# esp32_led.net
KiCad netlist of a schematic drawn in EAGLE
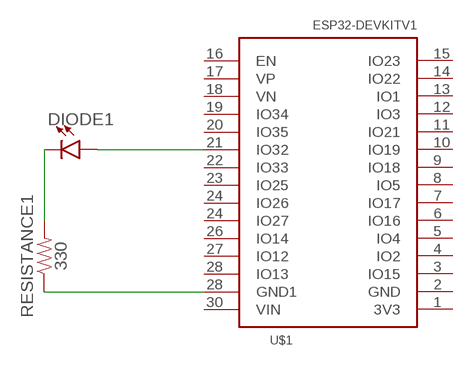
[diagram p0: schematic, sheet 1]

(export (version "E")
  (design (tool "Eeschema 10.0.6"))
  (components
    (comp (ref "DIODE1")
      (value "LED-3MM-NO_SILK")
      (footprint "eagle-import:LED_3MM-NS")
      (libsource (lib "eagle-import") (part "LED-3MM-NO_SILK"))
    )
    (comp (ref "RESISTANCE1")
      (value "330")
      (footprint "eagle-import:AXIAL-0.3")
      (libsource (lib "eagle-import") (part "330OHM-HORIZ-1/10W-5%"))
    )
    (comp (ref "U$1")
      (value "ESP32DEVKITV1")
      (footprint "eagle-import:ESP32-DEVKITV1")
      (libsource (lib "eagle-import") (part "ESP32DEVKITV1"))
    )
  )
  (nets
    (net (code "1") (name "Net-(DIODE1-C)") (class "Default")
      (node (ref "DIODE1") (pin "K") (pinfunction "C_K") (pintype "passive"))
      (node (ref "RESISTANCE1") (pin "P$2") (pinfunction "2_P$2") (pintype "passive"))
    )
    (net (code "2") (name "Net-(RESISTANCE1-1)") (class "Default")
      (node (ref "RESISTANCE1") (pin "P$1") (pinfunction "1_P$1") (pintype "passive"))
      (node (ref "U$1") (pin "28") (pinfunction "GND1_28") (pintype "bidirectional"))
    )
    (net (code "3") (name "Net-(U$1-IO32)") (class "Default")
      (node (ref "DIODE1") (pin "A") (pinfunction "A_A") (pintype "passive"))
      (node (ref "U$1") (pin "21") (pinfunction "IO32_21") (pintype "bidirectional"))
    )
    (net (code "4") (name "unconnected-(U$1-3V3-Pad1)") (class "Default")
      (node (ref "U$1") (pin "1") (pinfunction "3V3_1") (pintype "bidirectional"))
    )
    (net (code "5") (name "unconnected-(U$1-EN-Pad16)") (class "Default")
      (node (ref "U$1") (pin "16") (pinfunction "EN_16") (pintype "bidirectional"))
    )
    (net (code "6") (name "unconnected-(U$1-GND-Pad2)") (class "Default")
      (node (ref "U$1") (pin "2") (pinfunction "GND_2") (pintype "bidirectional"))
    )
    (net (code "7") (name "unconnected-(U$1-IO1-Pad13)") (class "Default")
      (node (ref "U$1") (pin "13") (pinfunction "IO1_13") (pintype "bidirectional"))
    )
    (net (code "8") (name "unconnected-(U$1-IO2-Pad4)") (class "Default")
      (node (ref "U$1") (pin "4") (pinfunction "IO2_4") (pintype "bidirectional"))
    )
    (net (code "9") (name "unconnected-(U$1-IO3-Pad12)") (class "Default")
      (node (ref "U$1") (pin "12") (pinfunction "IO3_12") (pintype "bidirectional"))
    )
    (net (code "10") (name "unconnected-(U$1-IO4-Pad5)") (class "Default")
      (node (ref "U$1") (pin "5") (pinfunction "IO4_5") (pintype "bidirectional"))
    )
    (net (code "11") (name "unconnected-(U$1-IO5-Pad8)") (class "Default")
      (node (ref "U$1") (pin "8") (pinfunction "IO5_8") (pintype "bidirectional"))
    )
    (net (code "12") (name "unconnected-(U$1-IO12-Pad27)") (class "Default")
      (node (ref "U$1") (pin "27") (pinfunction "IO12_27") (pintype "bidirectional"))
    )
    (net (code "13") (name "unconnected-(U$1-IO13-Pad28)") (class "Default")
      (node (ref "U$1") (pin "28") (pinfunction "IO13_28") (pintype "bidirectional"))
    )
    (net (code "14") (name "unconnected-(U$1-IO14-Pad26)") (class "Default")
      (node (ref "U$1") (pin "26") (pinfunction "IO14_26") (pintype "bidirectional"))
    )
    (net (code "15") (name "unconnected-(U$1-IO15-Pad3)") (class "Default")
      (node (ref "U$1") (pin "3") (pinfunction "IO15_3") (pintype "bidirectional"))
    )
    (net (code "16") (name "unconnected-(U$1-IO16-Pad6)") (class "Default")
      (node (ref "U$1") (pin "6") (pinfunction "IO16_6") (pintype "bidirectional"))
    )
    (net (code "17") (name "unconnected-(U$1-IO17-Pad7)") (class "Default")
      (node (ref "U$1") (pin "7") (pinfunction "IO17_7") (pintype "bidirectional"))
    )
    (net (code "18") (name "unconnected-(U$1-IO18-Pad9)") (class "Default")
      (node (ref "U$1") (pin "9") (pinfunction "IO18_9") (pintype "bidirectional"))
    )
    (net (code "19") (name "unconnected-(U$1-IO19-Pad10)") (class "Default")
      (node (ref "U$1") (pin "10") (pinfunction "IO19_10") (pintype "bidirectional"))
    )
    (net (code "20") (name "unconnected-(U$1-IO21-Pad11)") (class "Default")
      (node (ref "U$1") (pin "11") (pinfunction "IO21_11") (pintype "bidirectional"))
    )
    (net (code "21") (name "unconnected-(U$1-IO22-Pad14)") (class "Default")
      (node (ref "U$1") (pin "14") (pinfunction "IO22_14") (pintype "bidirectional"))
    )
    (net (code "22") (name "unconnected-(U$1-IO23-Pad15)") (class "Default")
      (node (ref "U$1") (pin "15") (pinfunction "IO23_15") (pintype "bidirectional"))
    )
    (net (code "23") (name "unconnected-(U$1-IO25-Pad23)") (class "Default")
      (node (ref "U$1") (pin "23") (pinfunction "IO25_23") (pintype "bidirectional"))
    )
    (net (code "24") (name "unconnected-(U$1-IO26-Pad24)") (class "Default")
      (node (ref "U$1") (pin "24") (pinfunction "IO26_24") (pintype "bidirectional"))
    )
    (net (code "25") (name "unconnected-(U$1-IO27-Pad24)") (class "Default")
      (node (ref "U$1") (pin "24") (pinfunction "IO27_24") (pintype "bidirectional"))
    )
    (net (code "26") (name "unconnected-(U$1-IO33-Pad22)") (class "Default")
      (node (ref "U$1") (pin "22") (pinfunction "IO33_22") (pintype "bidirectional"))
    )
    (net (code "27") (name "unconnected-(U$1-IO34-Pad19)") (class "Default")
      (node (ref "U$1") (pin "19") (pinfunction "IO34_19") (pintype "bidirectional"))
    )
    (net (code "28") (name "unconnected-(U$1-IO35-Pad20)") (class "Default")
      (node (ref "U$1") (pin "20") (pinfunction "IO35_20") (pintype "bidirectional"))
    )
    (net (code "29") (name "unconnected-(U$1-VIN-Pad30)") (class "Default")
      (node (ref "U$1") (pin "30") (pinfunction "VIN_30") (pintype "bidirectional"))
    )
    (net (code "30") (name "unconnected-(U$1-VN-Pad18)") (class "Default")
      (node (ref "U$1") (pin "18") (pinfunction "VN_18") (pintype "bidirectional"))
    )
    (net (code "31") (name "unconnected-(U$1-VP-Pad17)") (class "Default")
      (node (ref "U$1") (pin "17") (pinfunction "VP_17") (pintype "bidirectional"))
    )
  )
)
